# led_project.net
KiCad netlist of a schematic drawn in EasyEDA
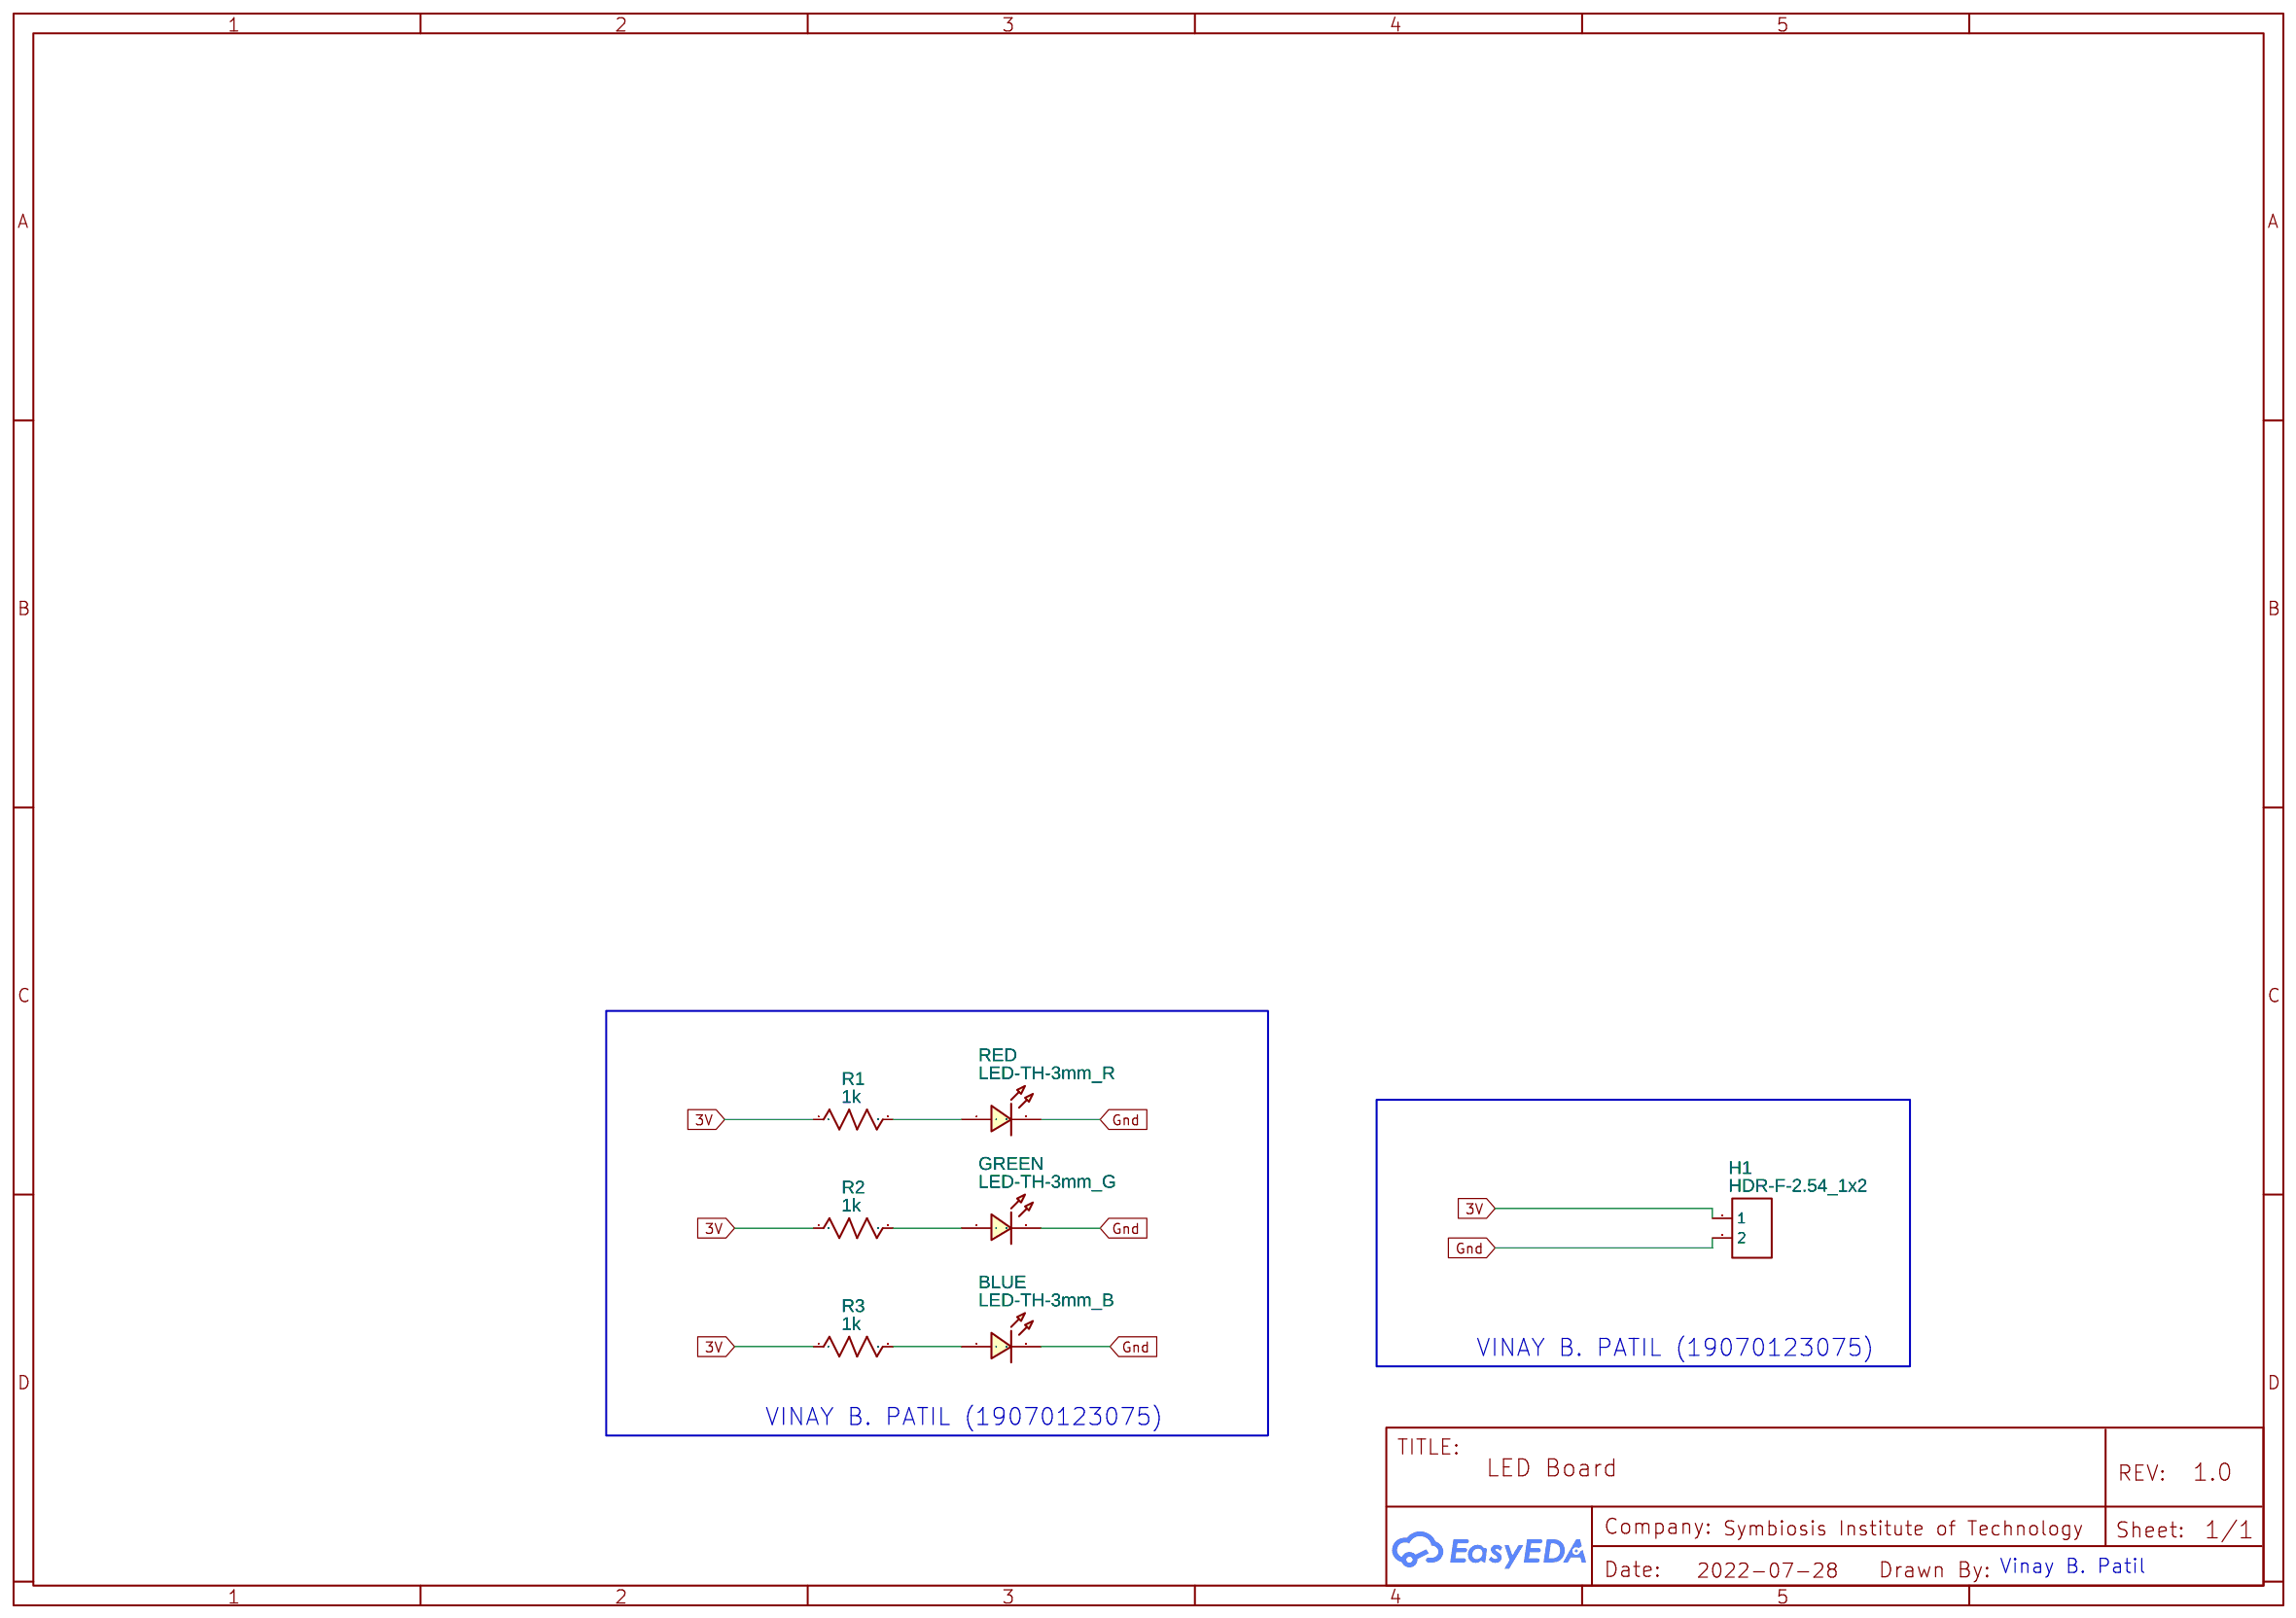
[diagram p0: schematic sheet]

(export (version "E")
  (design (tool "Eeschema 10.0.6"))
  (components
    (comp (ref "BLUE")
      (value "LED-TH-3mm_B")
      (fields
        (field (name "BOM_Manufacturer Part") "204-10SUBC/S400-A4")
        (field (name "BOM_Supplier Part") "C86881")
      )
      (libsource (lib "") (part "LED-TH-3mm_B"))
    )
    (comp (ref "GREEN")
      (value "LED-TH-3mm_G")
      (fields
        (field (name "BOM_Manufacturer Part") "204-10SYGD/S530-E3")
        (field (name "BOM_Supplier Part") "C85161")
      )
      (libsource (lib "") (part "LED-TH-3mm_G"))
    )
    (comp (ref "H1")
      (value "HDR-F-2.54_1x2")
      (fields (field (name "BOM_Supplier Part") "C49661"))
      (libsource (lib "") (part "HDR-F-2.54_1x2"))
    )
    (comp (ref "R1") (value "1k") (libsource (lib "") (part "R_AXIAL-0.3_US")))
    (comp (ref "R2") (value "1k") (libsource (lib "") (part "R_AXIAL-0.3_US")))
    (comp (ref "R3") (value "1k") (libsource (lib "") (part "R_AXIAL-0.3_US")))
    (comp (ref "RED")
      (value "LED-TH-3mm_R")
      (fields
        (field (name "BOM_Manufacturer Part") "204-10SDRD/S530-A3-L")
        (field (name "BOM_Supplier Part") "C84774")
      )
      (libsource (lib "") (part "LED-TH-3mm_R"))
    )
  )
  (nets
    (net (code "1") (name "3V") (class "Default")
      (node (ref "H1") (pin "1") (pinfunction "1_1") (pintype "input"))
      (node (ref "R1") (pin "1") (pinfunction "1_1") (pintype "unspecified"))
      (node (ref "R2") (pin "1") (pinfunction "1_1") (pintype "unspecified"))
      (node (ref "R3") (pin "1") (pinfunction "1_1") (pintype "unspecified"))
    )
    (net (code "2") (name "Gnd") (class "Default")
      (node (ref "BLUE") (pin "2") (pinfunction "2_2") (pintype "unspecified"))
      (node (ref "GREEN") (pin "2") (pinfunction "2_2") (pintype "unspecified"))
      (node (ref "H1") (pin "2") (pinfunction "2_2") (pintype "input"))
      (node (ref "RED") (pin "2") (pinfunction "2_2") (pintype "unspecified"))
    )
    (net (code "3") (name "Net-(BLUE-Pad1)") (class "Default")
      (node (ref "BLUE") (pin "1") (pinfunction "1_1") (pintype "unspecified"))
      (node (ref "R3") (pin "2") (pinfunction "2_2") (pintype "unspecified"))
    )
    (net (code "4") (name "Net-(GREEN-Pad1)") (class "Default")
      (node (ref "GREEN") (pin "1") (pinfunction "1_1") (pintype "unspecified"))
      (node (ref "R2") (pin "2") (pinfunction "2_2") (pintype "unspecified"))
    )
    (net (code "5") (name "Net-(R1-Pad2)") (class "Default")
      (node (ref "R1") (pin "2") (pinfunction "2_2") (pintype "unspecified"))
      (node (ref "RED") (pin "1") (pinfunction "1_1") (pintype "unspecified"))
    )
  )
)
